# amigaDIP48_2025-07-20.net
KiCad netlist of a schematic drawn in Altium Designer
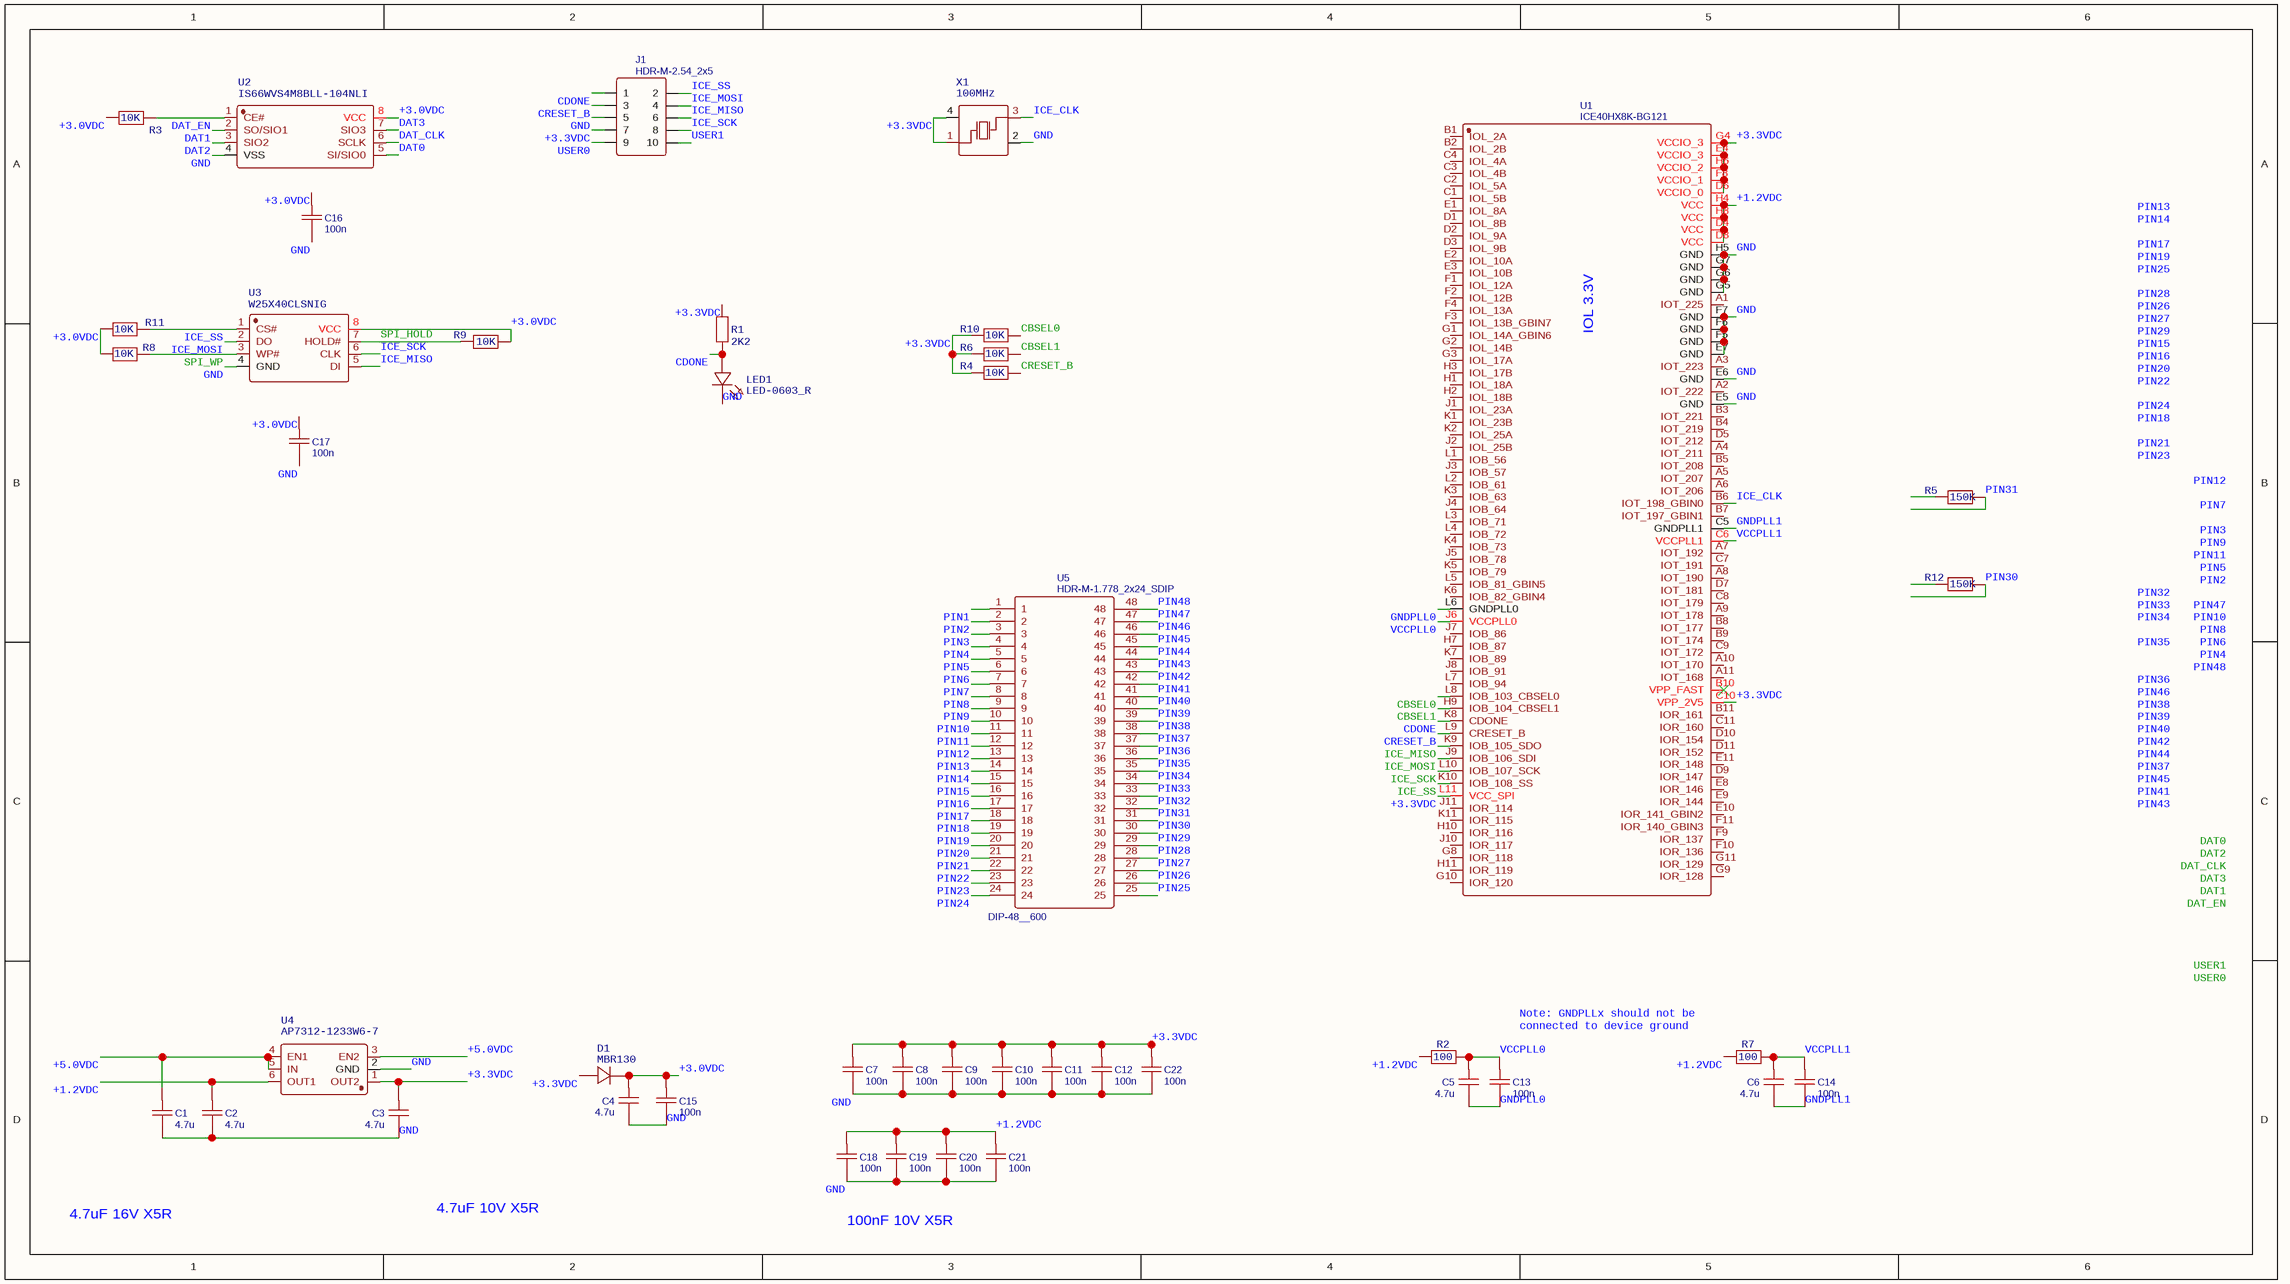
[diagram p0: amigaDIP48_2025-07-20.schdoc]

(export (version "E")
  (design (tool "Eeschema 10.0.6"))
  (components
    (comp (ref "C1")
      (value "4.7u")
      (fields
        (field (name "MANUFACTURER") "SAMSUNG(三星)")
        (field (name "MANUFACTURER PART") "CL05A475KP5NRNC")
        (field (name "CONTRIBUTOR") "LCSC")
      )
      (libsource (lib "") (part "root_0_4.7u__1"))
    )
    (comp (ref "C2")
      (value "4.7u")
      (fields
        (field (name "MANUFACTURER") "SAMSUNG(三星)")
        (field (name "MANUFACTURER PART") "CL05A475KP5NRNC")
        (field (name "CONTRIBUTOR") "LCSC")
      )
      (libsource (lib "") (part "root_0_4.7u__1"))
    )
    (comp (ref "C3")
      (value "4.7u")
      (fields
        (field (name "MANUFACTURER") "SAMSUNG(三星)")
        (field (name "MANUFACTURER PART") "CL05A475KP5NRNC")
        (field (name "CONTRIBUTOR") "LCSC")
      )
      (libsource (lib "altium-import") (part "root_0_4.7u_"))
    )
    (comp (ref "C4")
      (value "4.7u")
      (fields
        (field (name "MANUFACTURER") "SAMSUNG(三星)")
        (field (name "MANUFACTURER PART") "CL05A475KP5NRNC")
        (field (name "CONTRIBUTOR") "LCSC")
      )
      (libsource (lib "altium-import") (part "root_0_4.7u_"))
    )
    (comp (ref "C5")
      (value "4.7u")
      (fields
        (field (name "MANUFACTURER") "SAMSUNG(三星)")
        (field (name "MANUFACTURER PART") "CL05A475KP5NRNC")
        (field (name "CONTRIBUTOR") "LCSC")
      )
      (libsource (lib "altium-import") (part "root_0_4.7u_"))
    )
    (comp (ref "C6")
      (value "4.7u")
      (fields
        (field (name "MANUFACTURER") "SAMSUNG(三星)")
        (field (name "MANUFACTURER PART") "CL05A475KP5NRNC")
        (field (name "CONTRIBUTOR") "LCSC")
      )
      (libsource (lib "altium-import") (part "root_0_4.7u_"))
    )
    (comp (ref "C7")
      (value "100n")
      (fields
        (field (name "MANUFACTURER") "SAMSUNG(三星)")
        (field (name "MANUFACTURER PART") "CL03A104KP3NNNC")
      )
      (libsource (lib "altium-import") (part "root_1_100n_"))
    )
    (comp (ref "C8")
      (value "100n")
      (fields
        (field (name "MANUFACTURER") "SAMSUNG(三星)")
        (field (name "MANUFACTURER PART") "CL03A104KP3NNNC")
      )
      (libsource (lib "altium-import") (part "root_1_100n_"))
    )
    (comp (ref "C9")
      (value "100n")
      (fields
        (field (name "MANUFACTURER") "SAMSUNG(三星)")
        (field (name "MANUFACTURER PART") "CL03A104KP3NNNC")
      )
      (libsource (lib "altium-import") (part "root_1_100n_"))
    )
    (comp (ref "C10")
      (value "100n")
      (fields
        (field (name "MANUFACTURER") "SAMSUNG(三星)")
        (field (name "MANUFACTURER PART") "CL03A104KP3NNNC")
      )
      (libsource (lib "altium-import") (part "root_1_100n_"))
    )
    (comp (ref "C11")
      (value "100n")
      (fields
        (field (name "MANUFACTURER") "SAMSUNG(三星)")
        (field (name "MANUFACTURER PART") "CL03A104KP3NNNC")
      )
      (libsource (lib "altium-import") (part "root_1_100n_"))
    )
    (comp (ref "C12")
      (value "100n")
      (fields
        (field (name "MANUFACTURER") "SAMSUNG(三星)")
        (field (name "MANUFACTURER PART") "CL03A104KP3NNNC")
      )
      (libsource (lib "altium-import") (part "root_1_100n_"))
    )
    (comp (ref "C13")
      (value "100n")
      (fields
        (field (name "MANUFACTURER") "SAMSUNG(三星)")
        (field (name "MANUFACTURER PART") "CL03A104KP3NNNC")
      )
      (libsource (lib "altium-import") (part "root_1_100n_"))
    )
    (comp (ref "C14")
      (value "100n")
      (fields
        (field (name "MANUFACTURER") "SAMSUNG(三星)")
        (field (name "MANUFACTURER PART") "CL03A104KP3NNNC")
      )
      (libsource (lib "altium-import") (part "root_1_100n_"))
    )
    (comp (ref "C15")
      (value "100n")
      (fields
        (field (name "MANUFACTURER") "SAMSUNG(三星)")
        (field (name "MANUFACTURER PART") "CL03A104KP3NNNC")
      )
      (libsource (lib "altium-import") (part "root_1_100n_"))
    )
    (comp (ref "C16")
      (value "100n")
      (fields
        (field (name "MANUFACTURER") "SAMSUNG(三星)")
        (field (name "MANUFACTURER PART") "CL03A104KP3NNNC")
      )
      (libsource (lib "altium-import") (part "root_1_100n_"))
    )
    (comp (ref "C17")
      (value "100n")
      (fields
        (field (name "MANUFACTURER") "SAMSUNG(三星)")
        (field (name "MANUFACTURER PART") "CL03A104KP3NNNC")
      )
      (libsource (lib "altium-import") (part "root_1_100n_"))
    )
    (comp (ref "C18")
      (value "100n")
      (fields
        (field (name "MANUFACTURER") "SAMSUNG(三星)")
        (field (name "MANUFACTURER PART") "CL03A104KP3NNNC")
      )
      (libsource (lib "altium-import") (part "root_1_100n_"))
    )
    (comp (ref "C19")
      (value "100n")
      (fields
        (field (name "MANUFACTURER") "SAMSUNG(三星)")
        (field (name "MANUFACTURER PART") "CL03A104KP3NNNC")
      )
      (libsource (lib "altium-import") (part "root_1_100n_"))
    )
    (comp (ref "C20")
      (value "100n")
      (fields
        (field (name "MANUFACTURER") "SAMSUNG(三星)")
        (field (name "MANUFACTURER PART") "CL03A104KP3NNNC")
      )
      (libsource (lib "altium-import") (part "root_1_100n_"))
    )
    (comp (ref "C21")
      (value "100n")
      (fields
        (field (name "MANUFACTURER") "SAMSUNG(三星)")
        (field (name "MANUFACTURER PART") "CL03A104KP3NNNC")
      )
      (libsource (lib "altium-import") (part "root_1_100n_"))
    )
    (comp (ref "C22")
      (value "100n")
      (fields
        (field (name "MANUFACTURER") "SAMSUNG(三星)")
        (field (name "MANUFACTURER PART") "CL03A104KP3NNNC")
      )
      (libsource (lib "altium-import") (part "root_1_100n_"))
    )
    (comp (ref "D1")
      (value "MBR130")
      (fields (field (name "MANUFACTURER") "SK") (field (name "CONTRIBUTOR") "LCSC"))
      (libsource (lib "altium-import") (part "root_2_MBR130_"))
    )
    (comp (ref "J1")
      (value "HDR-M-2.54_2x5")
      (fields (field (name "CONTRIBUTOR") "LCEDA_Lib"))
      (libsource (lib "altium-import") (part "root_0_HDR-M-2.54_2x5_"))
    )
    (comp (ref "LED1")
      (value "LED-0603_R")
      (fields
        (field (name "MANUFACTURER") "EVERLIGHT(台湾亿光)")
        (field (name "MANUFACTURER PART") "19-217/R6C-AL1M2VY/3T")
        (field (name "CONTRIBUTOR") "LCEDA_01")
      )
      (libsource (lib "altium-import") (part "root_3_LED-0603_R_"))
    )
    (comp (ref "R1")
      (value "2K2")
      (fields
        (field (name "MANUFACTURER PART") "0402WGF1003TCE")
        (field (name "MANUFACTURER") "UniOhm")
        (field (name "CONTRIBUTOR") "LCEDA_Lib")
      )
      (libsource (lib "altium-import") (part "root_1_2K2_"))
    )
    (comp (ref "R2")
      (value "100")
      (fields
        (field (name "MANUFACTURER PART") "CR0201J100KQ15Z")
        (field (name "MANUFACTURER") "EVER OHMS(天二科技)")
        (field (name "CONTRIBUTOR") "LCEDA_Lib")
      )
      (libsource (lib "altium-import") (part "root_0_100_"))
    )
    (comp (ref "R3")
      (value "10K")
      (fields
        (field (name "MANUFACTURER PART") "CR0201F10K0Q15Z")
        (field (name "MANUFACTURER") "EVER OHMS(天二科技)")
        (field (name "CONTRIBUTOR") "LCEDA_Lib")
      )
      (libsource (lib "altium-import") (part "root_0_10K_"))
    )
    (comp (ref "R4")
      (value "10K")
      (fields
        (field (name "MANUFACTURER PART") "CR0201F10K0Q15Z")
        (field (name "MANUFACTURER") "EVER OHMS(天二科技)")
        (field (name "CONTRIBUTOR") "LCEDA_Lib")
      )
      (libsource (lib "altium-import") (part "root_0_10K_"))
    )
    (comp (ref "R5")
      (value "150K")
      (fields
        (field (name "MANUFACTURER PART") "WR02X154JAL")
        (field (name "MANUFACTURER") "Walsin(华新科)")
        (field (name "CONTRIBUTOR") "LCEDA_Lib")
      )
      (libsource (lib "altium-import") (part "root_0_150K_"))
    )
    (comp (ref "R6")
      (value "10K")
      (fields
        (field (name "MANUFACTURER PART") "CR0201F10K0Q15Z")
        (field (name "MANUFACTURER") "EVER OHMS(天二科技)")
        (field (name "CONTRIBUTOR") "LCEDA_Lib")
      )
      (libsource (lib "altium-import") (part "root_0_10K_"))
    )
    (comp (ref "R7")
      (value "100")
      (fields
        (field (name "MANUFACTURER PART") "CR0201J100KQ15Z")
        (field (name "MANUFACTURER") "EVER OHMS(天二科技)")
        (field (name "CONTRIBUTOR") "LCEDA_Lib")
      )
      (libsource (lib "altium-import") (part "root_0_100_"))
    )
    (comp (ref "R8")
      (value "10K")
      (fields
        (field (name "MANUFACTURER PART") "CR0201F10K0Q15Z")
        (field (name "MANUFACTURER") "EVER OHMS(天二科技)")
        (field (name "CONTRIBUTOR") "LCEDA_Lib")
      )
      (libsource (lib "altium-import") (part "root_0_10K_"))
    )
    (comp (ref "R9")
      (value "10K")
      (fields
        (field (name "MANUFACTURER PART") "CR0201F10K0Q15Z")
        (field (name "MANUFACTURER") "EVER OHMS(天二科技)")
        (field (name "CONTRIBUTOR") "LCEDA_Lib")
      )
      (libsource (lib "") (part "root_0_10K__1"))
    )
    (comp (ref "R10")
      (value "10K")
      (fields
        (field (name "MANUFACTURER PART") "CR0201F10K0Q15Z")
        (field (name "MANUFACTURER") "EVER OHMS(天二科技)")
        (field (name "CONTRIBUTOR") "LCEDA_Lib")
      )
      (libsource (lib "altium-import") (part "root_0_10K_"))
    )
    (comp (ref "R11")
      (value "10K")
      (fields
        (field (name "MANUFACTURER PART") "CR0201F10K0Q15Z")
        (field (name "MANUFACTURER") "EVER OHMS(天二科技)")
        (field (name "CONTRIBUTOR") "LCEDA_Lib")
      )
      (libsource (lib "altium-import") (part "root_0_10K_"))
    )
    (comp (ref "R12")
      (value "150K")
      (fields
        (field (name "MANUFACTURER PART") "WR02X154JAL")
        (field (name "MANUFACTURER") "Walsin(华新科)")
        (field (name "CONTRIBUTOR") "LCEDA_Lib")
      )
      (libsource (lib "altium-import") (part "root_0_150K_"))
    )
    (comp (ref "U1")
      (value "ICE40HX8K-BG121")
      (fields (field (name "MANUFACTURER") "LATTICE(莱迪思)") (field (name "CONTRIBUTOR") "LCSC"))
      (libsource (lib "altium-import") (part "root_0_ICE40HX8K-BG121_"))
    )
    (comp (ref "U2")
      (value "IS66WVS4M8BLL-104NLI")
      (fields (field (name "MANUFACTURER PART") "ESP-PSRAM64H") (field (name "CONTRIBUTOR") "LCSC"))
      (libsource (lib "altium-import") (part "root_0_IS66WVS4M8BLL-104NLI_"))
    )
    (comp (ref "U3")
      (value "W25X40CLSNIG")
      (fields (field (name "MANUFACTURER") "WINBOND"))
      (libsource (lib "altium-import") (part "root_0_W25X40CLSNIG_"))
    )
    (comp (ref "U4")
      (value "AP7312-1233W6-7")
      (fields
        (field (name "MANUFACTURER") "DIODES(美台)")
        (field (name "MANUFACTURER PART") "AP7312-1828W6-7")
        (field (name "CONTRIBUTOR") "lcsc")
      )
      (libsource (lib "altium-import") (part "root_2_AP7312-1233W6-7_"))
    )
    (comp (ref "U5")
      (value "HDR-M-1.778_2x24_SDIP")
      (fields (field (name "CONTRIBUTOR") "Renee"))
      (libsource (lib "altium-import") (part "root_0_HDR-M-1.778_2x24_SDIP_"))
    )
    (comp (ref "X1")
      (value "100MHz")
      (fields
        (field (name "MANUFACTURER") "TAITIEN Elec")
        (field (name "MANUFACTURER PART") "OXETDLJTNF-100.000000MHZ")
        (field (name "CONTRIBUTOR") "LCSC")
      )
      (libsource (lib "altium-import") (part "root_0_100MHz_"))
    )
  )
  (nets
    (net (code "1") (name "/+1.2VDC") (class "Default")
      (node (ref "C18") (pin "2") (pinfunction "2_2") (pintype "passive"))
      (node (ref "C19") (pin "2") (pinfunction "2_2") (pintype "passive"))
      (node (ref "C2") (pin "2") (pinfunction "2_2") (pintype "passive"))
      (node (ref "C20") (pin "2") (pinfunction "2_2") (pintype "passive"))
      (node (ref "C21") (pin "2") (pinfunction "2_2") (pintype "passive"))
      (node (ref "R2") (pin "1") (pinfunction "1_1") (pintype "passive"))
      (node (ref "R7") (pin "1") (pinfunction "1_1") (pintype "passive"))
      (node (ref "U1") (pin "D4") (pinfunction "VCC_D4") (pintype "passive"))
      (node (ref "U1") (pin "D8") (pinfunction "VCC_D8") (pintype "passive"))
      (node (ref "U1") (pin "H4") (pinfunction "VCC_H4") (pintype "passive"))
      (node (ref "U1") (pin "H8") (pinfunction "VCC_H8") (pintype "passive"))
      (node (ref "U4") (pin "6") (pinfunction "OUT1_6") (pintype "passive"))
    )
    (net (code "2") (name "/+3.0VDC") (class "Default")
      (node (ref "C15") (pin "2") (pinfunction "2_2") (pintype "passive"))
      (node (ref "C16") (pin "2") (pinfunction "2_2") (pintype "passive"))
      (node (ref "C17") (pin "2") (pinfunction "2_2") (pintype "passive"))
      (node (ref "C4") (pin "2") (pinfunction "2_2") (pintype "passive"))
      (node (ref "D1") (pin "1") (pinfunction "C_1") (pintype "passive"))
      (node (ref "R11") (pin "1") (pinfunction "1_1") (pintype "passive"))
      (node (ref "R3") (pin "1") (pinfunction "1_1") (pintype "passive"))
      (node (ref "R8") (pin "1") (pinfunction "1_1") (pintype "passive"))
      (node (ref "R9") (pin "1") (pinfunction "1_1") (pintype "passive"))
      (node (ref "U2") (pin "8") (pinfunction "VCC_8") (pintype "passive"))
      (node (ref "U3") (pin "8") (pinfunction "VCC_8") (pintype "passive"))
    )
    (net (code "3") (name "/+3.3VDC") (class "Default")
      (node (ref "C10") (pin "2") (pinfunction "2_2") (pintype "passive"))
      (node (ref "C11") (pin "2") (pinfunction "2_2") (pintype "passive"))
      (node (ref "C12") (pin "2") (pinfunction "2_2") (pintype "passive"))
      (node (ref "C22") (pin "2") (pinfunction "2_2") (pintype "passive"))
      (node (ref "C3") (pin "2") (pinfunction "2_2") (pintype "passive"))
      (node (ref "C7") (pin "2") (pinfunction "2_2") (pintype "passive"))
      (node (ref "C8") (pin "2") (pinfunction "2_2") (pintype "passive"))
      (node (ref "C9") (pin "2") (pinfunction "2_2") (pintype "passive"))
      (node (ref "D1") (pin "2") (pinfunction "A_2") (pintype "passive"))
      (node (ref "J1") (pin "7") (pinfunction "7_7") (pintype "passive"))
      (node (ref "R1") (pin "2") (pinfunction "2_2") (pintype "passive"))
      (node (ref "R10") (pin "1") (pinfunction "1_1") (pintype "passive"))
      (node (ref "R4") (pin "1") (pinfunction "1_1") (pintype "passive"))
      (node (ref "R6") (pin "1") (pinfunction "1_1") (pintype "passive"))
      (node (ref "U1") (pin "C10") (pinfunction "VPP_2V5_C10") (pintype "passive"))
      (node (ref "U1") (pin "D6") (pinfunction "VCCIO_0_D6") (pintype "passive"))
      (node (ref "U1") (pin "E4") (pinfunction "VCCIO_3_E4") (pintype "passive"))
      (node (ref "U1") (pin "F8") (pinfunction "VCCIO_1_F8") (pintype "passive"))
      (node (ref "U1") (pin "G4") (pinfunction "VCCIO_3_G4") (pintype "passive"))
      (node (ref "U1") (pin "H6") (pinfunction "VCCIO_2_H6") (pintype "passive"))
      (node (ref "U1") (pin "L11") (pinfunction "VCC_SPI_L11") (pintype "passive"))
      (node (ref "U4") (pin "1") (pinfunction "OUT2_1") (pintype "passive"))
      (node (ref "X1") (pin "1") (pinfunction "OSC1_1") (pintype "passive"))
      (node (ref "X1") (pin "4") (pinfunction "GND_4") (pintype "passive"))
    )
    (net (code "4") (name "/+5.0VDC") (class "Default")
      (node (ref "C1") (pin "2") (pinfunction "2_2") (pintype "passive"))
      (node (ref "U4") (pin "3") (pinfunction "EN2_3") (pintype "passive"))
      (node (ref "U4") (pin "4") (pinfunction "EN1_4") (pintype "passive"))
      (node (ref "U4") (pin "5") (pinfunction "IN_5") (pintype "passive"))
    )
    (net (code "5") (name "/CBSEL0") (class "Default")
      (node (ref "R10") (pin "2") (pinfunction "2_2") (pintype "passive"))
      (node (ref "U1") (pin "L8") (pinfunction "IOB_103_CBSEL0_L8") (pintype "passive"))
    )
    (net (code "6") (name "/CBSEL1") (class "Default")
      (node (ref "R6") (pin "2") (pinfunction "2_2") (pintype "passive"))
      (node (ref "U1") (pin "H9") (pinfunction "IOB_104_CBSEL1_H9") (pintype "passive"))
    )
    (net (code "7") (name "/CDONE") (class "Default")
      (node (ref "J1") (pin "1") (pinfunction "1_1") (pintype "passive"))
      (node (ref "LED1") (pin "1") (pinfunction "1_1") (pintype "passive"))
      (node (ref "R1") (pin "1") (pinfunction "1_1") (pintype "passive"))
      (node (ref "U1") (pin "K8") (pinfunction "CDONE_K8") (pintype "passive"))
    )
    (net (code "8") (name "/CRESET_B") (class "Default")
      (node (ref "J1") (pin "3") (pinfunction "3_3") (pintype "passive"))
      (node (ref "R4") (pin "2") (pinfunction "2_2") (pintype "passive"))
      (node (ref "U1") (pin "L9") (pinfunction "CRESET_B_L9") (pintype "passive"))
    )
    (net (code "9") (name "/DAT0") (class "Default")
      (node (ref "U2") (pin "5") (pinfunction "SI/SIO0_5") (pintype "passive"))
    )
    (net (code "10") (name "/DAT1") (class "Default")
      (node (ref "U2") (pin "2") (pinfunction "SO/SIO1_2") (pintype "passive"))
    )
    (net (code "11") (name "/DAT2") (class "Default")
      (node (ref "U2") (pin "3") (pinfunction "SIO2_3") (pintype "passive"))
    )
    (net (code "12") (name "/DAT3") (class "Default")
      (node (ref "U2") (pin "7") (pinfunction "SIO3_7") (pintype "passive"))
    )
    (net (code "13") (name "/DAT_CLK") (class "Default")
      (node (ref "U2") (pin "6") (pinfunction "SCLK_6") (pintype "passive"))
    )
    (net (code "14") (name "/DAT_EN") (class "Default")
      (node (ref "R3") (pin "2") (pinfunction "2_2") (pintype "passive"))
      (node (ref "U2") (pin "1") (pinfunction "CE#_1") (pintype "passive"))
    )
    (net (code "15") (name "/GND") (class "Default")
      (node (ref "C1") (pin "1") (pinfunction "1_1") (pintype "passive"))
      (node (ref "C10") (pin "1") (pinfunction "1_1") (pintype "passive"))
      (node (ref "C11") (pin "1") (pinfunction "1_1") (pintype "passive"))
      (node (ref "C12") (pin "1") (pinfunction "1_1") (pintype "passive"))
      (node (ref "C15") (pin "1") (pinfunction "1_1") (pintype "passive"))
      (node (ref "C16") (pin "1") (pinfunction "1_1") (pintype "passive"))
      (node (ref "C17") (pin "1") (pinfunction "1_1") (pintype "passive"))
      (node (ref "C18") (pin "1") (pinfunction "1_1") (pintype "passive"))
      (node (ref "C19") (pin "1") (pinfunction "1_1") (pintype "passive"))
      (node (ref "C2") (pin "1") (pinfunction "1_1") (pintype "passive"))
      (node (ref "C20") (pin "1") (pinfunction "1_1") (pintype "passive"))
      (node (ref "C21") (pin "1") (pinfunction "1_1") (pintype "passive"))
      (node (ref "C22") (pin "1") (pinfunction "1_1") (pintype "passive"))
      (node (ref "C3") (pin "1") (pinfunction "1_1") (pintype "passive"))
      (node (ref "C4") (pin "1") (pinfunction "1_1") (pintype "passive"))
      (node (ref "C7") (pin "1") (pinfunction "1_1") (pintype "passive"))
      (node (ref "C8") (pin "1") (pinfunction "1_1") (pintype "passive"))
      (node (ref "C9") (pin "1") (pinfunction "1_1") (pintype "passive"))
      (node (ref "J1") (pin "5") (pinfunction "5_5") (pintype "passive"))
      (node (ref "LED1") (pin "2") (pinfunction "2_2") (pintype "passive"))
      (node (ref "U1") (pin "E5") (pinfunction "GND_E5") (pintype "passive"))
      (node (ref "U1") (pin "E6") (pinfunction "GND_E6") (pintype "passive"))
      (node (ref "U1") (pin "E7") (pinfunction "GND_E7") (pintype "passive"))
      (node (ref "U1") (pin "F5") (pinfunction "GND_F5") (pintype "passive"))
      (node (ref "U1") (pin "F6") (pinfunction "GND_F6") (pintype "passive"))
      (node (ref "U1") (pin "F7") (pinfunction "GND_F7") (pintype "passive"))
      (node (ref "U1") (pin "G5") (pinfunction "GND_G5") (pintype "passive"))
      (node (ref "U1") (pin "G6") (pinfunction "GND_G6") (pintype "passive"))
      (node (ref "U1") (pin "G7") (pinfunction "GND_G7") (pintype "passive"))
      (node (ref "U1") (pin "H5") (pinfunction "GND_H5") (pintype "passive"))
      (node (ref "U2") (pin "4") (pinfunction "VSS_4") (pintype "passive"))
      (node (ref "U3") (pin "4") (pinfunction "GND_4") (pintype "passive"))
      (node (ref "U4") (pin "2") (pinfunction "GND_2") (pintype "passive"))
      (node (ref "X1") (pin "2") (pinfunction "GND_2") (pintype "passive"))
    )
    (net (code "16") (name "/GNDPLL0") (class "Default")
      (node (ref "C13") (pin "1") (pinfunction "1_1") (pintype "passive"))
      (node (ref "C5") (pin "1") (pinfunction "1_1") (pintype "passive"))
      (node (ref "U1") (pin "L6") (pinfunction "GNDPLL0_L6") (pintype "passive"))
    )
    (net (code "17") (name "/GNDPLL1") (class "Default")
      (node (ref "C14") (pin "1") (pinfunction "1_1") (pintype "passive"))
      (node (ref "C6") (pin "1") (pinfunction "1_1") (pintype "passive"))
      (node (ref "U1") (pin "C5") (pinfunction "GNDPLL1_C5") (pintype "passive"))
    )
    (net (code "18") (name "/ICE_CLK") (class "Default")
      (node (ref "U1") (pin "B6") (pinfunction "IOT_198_GBIN0_B6") (pintype "passive"))
      (node (ref "X1") (pin "3") (pinfunction "OSC2_3") (pintype "passive"))
    )
    (net (code "19") (name "/ICE_MISO") (class "Default")
      (node (ref "J1") (pin "6") (pinfunction "6_6") (pintype "passive"))
      (node (ref "U1") (pin "K9") (pinfunction "IOB_105_SDO_K9") (pintype "passive"))
      (node (ref "U3") (pin "5") (pinfunction "DI_5") (pintype "passive"))
    )
    (net (code "20") (name "/ICE_MOSI") (class "Default")
      (node (ref "J1") (pin "4") (pinfunction "4_4") (pintype "passive"))
      (node (ref "U1") (pin "J9") (pinfunction "IOB_106_SDI_J9") (pintype "passive"))
      (node (ref "U3") (pin "2") (pinfunction "DO_2") (pintype "passive"))
    )
    (net (code "21") (name "/ICE_SCK") (class "Default")
      (node (ref "J1") (pin "8") (pinfunction "8_8") (pintype "passive"))
      (node (ref "U1") (pin "L10") (pinfunction "IOB_107_SCK_L10") (pintype "passive"))
      (node (ref "U3") (pin "6") (pinfunction "CLK_6") (pintype "passive"))
    )
    (net (code "22") (name "/ICE_SS") (class "Default")
      (node (ref "J1") (pin "2") (pinfunction "2_2") (pintype "passive"))
      (node (ref "R11") (pin "2") (pinfunction "2_2") (pintype "passive"))
      (node (ref "U1") (pin "K10") (pinfunction "IOB_108_SS_K10") (pintype "passive"))
      (node (ref "U3") (pin "1") (pinfunction "CS#_1") (pintype "passive"))
    )
    (net (code "23") (name "/PIN1") (class "Default")
      (node (ref "U5") (pin "1") (pinfunction "1_1") (pintype "passive"))
    )
    (net (code "24") (name "/PIN2") (class "Default")
      (node (ref "U5") (pin "2") (pinfunction "2_2") (pintype "passive"))
    )
    (net (code "25") (name "/PIN3") (class "Default")
      (node (ref "U5") (pin "3") (pinfunction "3_3") (pintype "passive"))
    )
    (net (code "26") (name "/PIN4") (class "Default")
      (node (ref "U5") (pin "4") (pinfunction "4_4") (pintype "passive"))
    )
    (net (code "27") (name "/PIN5") (class "Default")
      (node (ref "U5") (pin "5") (pinfunction "5_5") (pintype "passive"))
    )
    (net (code "28") (name "/PIN6") (class "Default")
      (node (ref "U5") (pin "6") (pinfunction "6_6") (pintype "passive"))
    )
    (net (code "29") (name "/PIN7") (class "Default")
      (node (ref "U5") (pin "7") (pinfunction "7_7") (pintype "passive"))
    )
    (net (code "30") (name "/PIN8") (class "Default")
      (node (ref "U5") (pin "8") (pinfunction "8_8") (pintype "passive"))
    )
    (net (code "31") (name "/PIN9") (class "Default")
      (node (ref "U5") (pin "9") (pinfunction "9_9") (pintype "passive"))
    )
    (net (code "32") (name "/PIN10") (class "Default")
      (node (ref "U5") (pin "10") (pinfunction "10_10") (pintype "passive"))
    )
    (net (code "33") (name "/PIN11") (class "Default")
      (node (ref "U5") (pin "11") (pinfunction "11_11") (pintype "passive"))
    )
    (net (code "34") (name "/PIN12") (class "Default")
      (node (ref "U5") (pin "12") (pinfunction "12_12") (pintype "passive"))
    )
    (net (code "35") (name "/PIN13") (class "Default")
      (node (ref "U5") (pin "13") (pinfunction "13_13") (pintype "passive"))
    )
    (net (code "36") (name "/PIN14") (class "Default")
      (node (ref "U5") (pin "14") (pinfunction "14_14") (pintype "passive"))
    )
    (net (code "37") (name "/PIN15") (class "Default")
      (node (ref "U5") (pin "15") (pinfunction "15_15") (pintype "passive"))
    )
    (net (code "38") (name "/PIN16") (class "Default")
      (node (ref "U5") (pin "16") (pinfunction "16_16") (pintype "passive"))
    )
    (net (code "39") (name "/PIN17") (class "Default")
      (node (ref "U5") (pin "17") (pinfunction "17_17") (pintype "passive"))
    )
    (net (code "40") (name "/PIN18") (class "Default")
      (node (ref "U5") (pin "18") (pinfunction "18_18") (pintype "passive"))
    )
    (net (code "41") (name "/PIN19") (class "Default")
      (node (ref "U5") (pin "19") (pinfunction "19_19") (pintype "passive"))
    )
    (net (code "42") (name "/PIN20") (class "Default")
      (node (ref "U5") (pin "20") (pinfunction "20_20") (pintype "passive"))
    )
    (net (code "43") (name "/PIN21") (class "Default")
      (node (ref "U5") (pin "21") (pinfunction "21_21") (pintype "passive"))
    )
    (net (code "44") (name "/PIN22") (class "Default")
      (node (ref "U5") (pin "22") (pinfunction "22_22") (pintype "passive"))
    )
    (net (code "45") (name "/PIN23") (class "Default")
      (node (ref "U5") (pin "23") (pinfunction "23_23") (pintype "passive"))
    )
    (net (code "46") (name "/PIN24") (class "Default")
      (node (ref "U5") (pin "24") (pinfunction "24_24") (pintype "passive"))
    )
    (net (code "47") (name "/PIN25") (class "Default")
      (node (ref "U5") (pin "25") (pinfunction "25_25") (pintype "passive"))
    )
    (net (code "48") (name "/PIN26") (class "Default")
      (node (ref "U5") (pin "26") (pinfunction "26_26") (pintype "passive"))
    )
    (net (code "49") (name "/PIN27") (class "Default")
      (node (ref "U5") (pin "27") (pinfunction "27_27") (pintype "passive"))
    )
    (net (code "50") (name "/PIN28") (class "Default")
      (node (ref "U5") (pin "28") (pinfunction "28_28") (pintype "passive"))
    )
    (net (code "51") (name "/PIN29") (class "Default")
      (node (ref "U5") (pin "29") (pinfunction "29_29") (pintype "passive"))
    )
    (net (code "52") (name "/PIN30") (class "Default")
      (node (ref "R12") (pin "2") (pinfunction "2_2") (pintype "passive"))
      (node (ref "U5") (pin "30") (pinfunction "30_30") (pintype "passive"))
    )
    (net (code "53") (name "/PIN31") (class "Default")
      (node (ref "R5") (pin "2") (pinfunction "2_2") (pintype "passive"))
      (node (ref "U5") (pin "31") (pinfunction "31_31") (pintype "passive"))
    )
    (net (code "54") (name "/PIN32") (class "Default")
      (node (ref "U5") (pin "32") (pinfunction "32_32") (pintype "passive"))
    )
    (net (code "55") (name "/PIN33") (class "Default")
      (node (ref "U5") (pin "33") (pinfunction "33_33") (pintype "passive"))
    )
    (net (code "56") (name "/PIN34") (class "Default")
      (node (ref "U5") (pin "34") (pinfunction "34_34") (pintype "passive"))
    )
    (net (code "57") (name "/PIN35") (class "Default")
      (node (ref "U5") (pin "35") (pinfunction "35_35") (pintype "passive"))
    )
    (net (code "58") (name "/PIN36") (class "Default")
      (node (ref "U5") (pin "36") (pinfunction "36_36") (pintype "passive"))
    )
    (net (code "59") (name "/PIN37") (class "Default")
      (node (ref "U5") (pin "37") (pinfunction "37_37") (pintype "passive"))
    )
    (net (code "60") (name "/PIN38") (class "Default")
      (node (ref "U5") (pin "38") (pinfunction "38_38") (pintype "passive"))
    )
    (net (code "61") (name "/PIN39") (class "Default")
      (node (ref "U5") (pin "39") (pinfunction "39_39") (pintype "passive"))
    )
    (net (code "62") (name "/PIN40") (class "Default")
      (node (ref "U5") (pin "40") (pinfunction "40_40") (pintype "passive"))
    )
    (net (code "63") (name "/PIN41") (class "Default")
      (node (ref "U5") (pin "41") (pinfunction "41_41") (pintype "passive"))
    )
    (net (code "64") (name "/PIN42") (class "Default")
      (node (ref "U5") (pin "42") (pinfunction "42_42") (pintype "passive"))
    )
    (net (code "65") (name "/PIN43") (class "Default")
      (node (ref "U5") (pin "43") (pinfunction "43_43") (pintype "passive"))
    )
    (net (code "66") (name "/PIN44") (class "Default")
      (node (ref "U5") (pin "44") (pinfunction "44_44") (pintype "passive"))
    )
    (net (code "67") (name "/PIN45") (class "Default")
      (node (ref "U5") (pin "45") (pinfunction "45_45") (pintype "passive"))
    )
    (net (code "68") (name "/PIN46") (class "Default")
      (node (ref "U5") (pin "46") (pinfunction "46_46") (pintype "passive"))
    )
    (net (code "69") (name "/PIN47") (class "Default")
      (node (ref "U5") (pin "47") (pinfunction "47_47") (pintype "passive"))
    )
    (net (code "70") (name "/PIN48") (class "Default")
      (node (ref "U5") (pin "48") (pinfunction "48_48") (pintype "passive"))
    )
    (net (code "71") (name "/SPI_HOLD") (class "Default")
      (node (ref "R9") (pin "2") (pinfunction "2_2") (pintype "passive"))
      (node (ref "U3") (pin "7") (pinfunction "HOLD#_7") (pintype "passive"))
    )
    (net (code "72") (name "/SPI_WP") (class "Default")
      (node (ref "R8") (pin "2") (pinfunction "2_2") (pintype "passive"))
      (node (ref "U3") (pin "3") (pinfunction "WP#_3") (pintype "passive"))
    )
    (net (code "73") (name "/USER0") (class "Default")
      (node (ref "J1") (pin "9") (pinfunction "9_9") (pintype "passive"))
    )
    (net (code "74") (name "/USER1") (class "Default")
      (node (ref "J1") (pin "10") (pinfunction "10_10") (pintype "passive"))
    )
    (net (code "75") (name "/VCCPLL0") (class "Default")
      (node (ref "C13") (pin "2") (pinfunction "2_2") (pintype "passive"))
      (node (ref "C5") (pin "2") (pinfunction "2_2") (pintype "passive"))
      (node (ref "R2") (pin "2") (pinfunction "2_2") (pintype "passive"))
      (node (ref "U1") (pin "J6") (pinfunction "VCCPLL0_J6") (pintype "passive"))
    )
    (net (code "76") (name "/VCCPLL1") (class "Default")
      (node (ref "C14") (pin "2") (pinfunction "2_2") (pintype "passive"))
      (node (ref "C6") (pin "2") (pinfunction "2_2") (pintype "passive"))
      (node (ref "R7") (pin "2") (pinfunction "2_2") (pintype "passive"))
      (node (ref "U1") (pin "C6") (pinfunction "VCCPLL1_C6") (pintype "passive"))
    )
    (net (code "77") (name "unconnected-(R5-Pad1)") (class "Default")
      (node (ref "R5") (pin "1") (pinfunction "1_1") (pintype "passive"))
    )
    (net (code "78") (name "unconnected-(R12-Pad1)") (class "Default")
      (node (ref "R12") (pin "1") (pinfunction "1_1") (pintype "passive"))
    )
    (net (code "79") (name "unconnected-(U1-IOB_56-PadL1)") (class "Default")
      (node (ref "U1") (pin "L1") (pinfunction "IOB_56_L1") (pintype "passive"))
    )
    (net (code "80") (name "unconnected-(U1-IOB_57-PadJ3)") (class "Default")
      (node (ref "U1") (pin "J3") (pinfunction "IOB_57_J3") (pintype "passive"))
    )
    (net (code "81") (name "unconnected-(U1-IOB_61-PadL2)") (class "Default")
      (node (ref "U1") (pin "L2") (pinfunction "IOB_61_L2") (pintype "passive"))
    )
    (net (code "82") (name "unconnected-(U1-IOB_63-PadK3)") (class "Default")
      (node (ref "U1") (pin "K3") (pinfunction "IOB_63_K3") (pintype "passive"))
    )
    (net (code "83") (name "unconnected-(U1-IOB_64-PadJ4)") (class "Default")
      (node (ref "U1") (pin "J4") (pinfunction "IOB_64_J4") (pintype "passive"))
    )
    (net (code "84") (name "unconnected-(U1-IOB_71-PadL3)") (class "Default")
      (node (ref "U1") (pin "L3") (pinfunction "IOB_71_L3") (pintype "passive"))
    )
    (net (code "85") (name "unconnected-(U1-IOB_72-PadL4)") (class "Default")
      (node (ref "U1") (pin "L4") (pinfunction "IOB_72_L4") (pintype "passive"))
    )
    (net (code "86") (name "unconnected-(U1-IOB_73-PadK4)") (class "Default")
      (node (ref "U1") (pin "K4") (pinfunction "IOB_73_K4") (pintype "passive"))
    )
    (net (code "87") (name "unconnected-(U1-IOB_78-PadJ5)") (class "Default")
      (node (ref "U1") (pin "J5") (pinfunction "IOB_78_J5") (pintype "passive"))
    )
    (net (code "88") (name "unconnected-(U1-IOB_79-PadK5)") (class "Default")
      (node (ref "U1") (pin "K5") (pinfunction "IOB_79_K5") (pintype "passive"))
    )
    (net (code "89") (name "unconnected-(U1-IOB_81_GBIN5-PadL5)") (class "Default")
      (node (ref "U1") (pin "L5") (pinfunction "IOB_81_GBIN5_L5") (pintype "passive"))
    )
    (net (code "90") (name "unconnected-(U1-IOB_82_GBIN4-PadK6)") (class "Default")
      (node (ref "U1") (pin "K6") (pinfunction "IOB_82_GBIN4_K6") (pintype "passive"))
    )
    (net (code "91") (name "unconnected-(U1-IOB_86-PadJ7)") (class "Default")
      (node (ref "U1") (pin "J7") (pinfunction "IOB_86_J7") (pintype "passive"))
    )
    (net (code "92") (name "unconnected-(U1-IOB_87-PadH7)") (class "Default")
      (node (ref "U1") (pin "H7") (pinfunction "IOB_87_H7") (pintype "passive"))
    )
    (net (code "93") (name "unconnected-(U1-IOB_89-PadK7)") (class "Default")
      (node (ref "U1") (pin "K7") (pinfunction "IOB_89_K7") (pintype "passive"))
    )
    (net (code "94") (name "unconnected-(U1-IOB_91-PadJ8)") (class "Default")
      (node (ref "U1") (pin "J8") (pinfunction "IOB_91_J8") (pintype "passive"))
    )
    (net (code "95") (name "unconnected-(U1-IOB_94-PadL7)") (class "Default")
      (node (ref "U1") (pin "L7") (pinfunction "IOB_94_L7") (pintype "passive"))
    )
    (net (code "96") (name "unconnected-(U1-IOL_2A-PadB1)") (class "Default")
      (node (ref "U1") (pin "B1") (pinfunction "IOL_2A_B1") (pintype "passive"))
    )
    (net (code "97") (name "unconnected-(U1-IOL_2B-PadB2)") (class "Default")
      (node (ref "U1") (pin "B2") (pinfunction "IOL_2B_B2") (pintype "passive"))
    )
    (net (code "98") (name "unconnected-(U1-IOL_4A-PadC4)") (class "Default")
      (node (ref "U1") (pin "C4") (pinfunction "IOL_4A_C4") (pintype "passive"))
    )
    (net (code "99") (name "unconnected-(U1-IOL_4B-PadC3)") (class "Default")
      (node (ref "U1") (pin "C3") (pinfunction "IOL_4B_C3") (pintype "passive"))
    )
    (net (code "100") (name "unconnected-(U1-IOL_5A-PadC2)") (class "Default")
      (node (ref "U1") (pin "C2") (pinfunction "IOL_5A_C2") (pintype "passive"))
    )
    (net (code "101") (name "unconnected-(U1-IOL_5B-PadC1)") (class "Default")
      (node (ref "U1") (pin "C1") (pinfunction "IOL_5B_C1") (pintype "passive"))
    )
    (net (code "102") (name "unconnected-(U1-IOL_8A-PadE1)") (class "Default")
      (node (ref "U1") (pin "E1") (pinfunction "IOL_8A_E1") (pintype "passive"))
    )
    (net (code "103") (name "unconnected-(U1-IOL_8B-PadD1)") (class "Default")
      (node (ref "U1") (pin "D1") (pinfunction "IOL_8B_D1") (pintype "passive"))
    )
    (net (code "104") (name "unconnected-(U1-IOL_9A-PadD2)") (class "Default")
      (node (ref "U1") (pin "D2") (pinfunction "IOL_9A_D2") (pintype "passive"))
    )
    (net (code "105") (name "unconnected-(U1-IOL_9B-PadD3)") (class "Default")
      (node (ref "U1") (pin "D3") (pinfunction "IOL_9B_D3") (pintype "passive"))
    )
    (net (code "106") (name "unconnected-(U1-IOL_10A-PadE2)") (class "Default")
      (node (ref "U1") (pin "E2") (pinfunction "IOL_10A_E2") (pintype "passive"))
    )
    (net (code "107") (name "unconnected-(U1-IOL_10B-PadE3)") (class "Default")
      (node (ref "U1") (pin "E3") (pinfunction "IOL_10B_E3") (pintype "passive"))
    )
    (net (code "108") (name "unconnected-(U1-IOL_12A-PadF1)") (class "Default")
      (node (ref "U1") (pin "F1") (pinfunction "IOL_12A_F1") (pintype "passive"))
    )
    (net (code "109") (name "unconnected-(U1-IOL_12B-PadF2)") (class "Default")
      (node (ref "U1") (pin "F2") (pinfunction "IOL_12B_F2") (pintype "passive"))
    )
    (net (code "110") (name "unconnected-(U1-IOL_13A-PadF4)") (class "Default")
      (node (ref "U1") (pin "F4") (pinfunction "IOL_13A_F4") (pintype "passive"))
    )
    (net (code "111") (name "unconnected-(U1-IOL_13B_GBIN7-PadF3)") (class "Default")
      (node (ref "U1") (pin "F3") (pinfunction "IOL_13B_GBIN7_F3") (pintype "passive"))
    )
    (net (code "112") (name "unconnected-(U1-IOL_14A_GBIN6-PadG1)") (class "Default")
      (node (ref "U1") (pin "G1") (pinfunction "IOL_14A_GBIN6_G1") (pintype "passive"))
    )
    (net (code "113") (name "unconnected-(U1-IOL_14B-PadG2)") (class "Default")
      (node (ref "U1") (pin "G2") (pinfunction "IOL_14B_G2") (pintype "passive"))
    )
    (net (code "114") (name "unconnected-(U1-IOL_17A-PadG3)") (class "Default")
      (node (ref "U1") (pin "G3") (pinfunction "IOL_17A_G3") (pintype "passive"))
    )
    (net (code "115") (name "unconnected-(U1-IOL_17B-PadH3)") (class "Default")
      (node (ref "U1") (pin "H3") (pinfunction "IOL_17B_H3") (pintype "passive"))
    )
    (net (code "116") (name "unconnected-(U1-IOL_18A-PadH1)") (class "Default")
      (node (ref "U1") (pin "H1") (pinfunction "IOL_18A_H1") (pintype "passive"))
    )
    (net (code "117") (name "unconnected-(U1-IOL_18B-PadH2)") (class "Default")
      (node (ref "U1") (pin "H2") (pinfunction "IOL_18B_H2") (pintype "passive"))
    )
    (net (code "118") (name "unconnected-(U1-IOL_23A-PadJ1)") (class "Default")
      (node (ref "U1") (pin "J1") (pinfunction "IOL_23A_J1") (pintype "passive"))
    )
    (net (code "119") (name "unconnected-(U1-IOL_23B-PadK1)") (class "Default")
      (node (ref "U1") (pin "K1") (pinfunction "IOL_23B_K1") (pintype "passive"))
    )
    (net (code "120") (name "unconnected-(U1-IOL_25A-PadK2)") (class "Default")
      (node (ref "U1") (pin "K2") (pinfunction "IOL_25A_K2") (pintype "passive"))
    )
    (net (code "121") (name "unconnected-(U1-IOL_25B-PadJ2)") (class "Default")
      (node (ref "U1") (pin "J2") (pinfunction "IOL_25B_J2") (pintype "passive"))
    )
    (net (code "122") (name "unconnected-(U1-IOR_114-PadJ11)") (class "Default")
      (node (ref "U1") (pin "J11") (pinfunction "IOR_114_J11") (pintype "passive"))
    )
    (net (code "123") (name "unconnected-(U1-IOR_115-PadK11)") (class "Default")
      (node (ref "U1") (pin "K11") (pinfunction "IOR_115_K11") (pintype "passive"))
    )
    (net (code "124") (name "unconnected-(U1-IOR_116-PadH10)") (class "Default")
      (node (ref "U1") (pin "H10") (pinfunction "IOR_116_H10") (pintype "passive"))
    )
    (net (code "125") (name "unconnected-(U1-IOR_117-PadJ10)") (class "Default")
      (node (ref "U1") (pin "J10") (pinfunction "IOR_117_J10") (pintype "passive"))
    )
    (net (code "126") (name "unconnected-(U1-IOR_118-PadG8)") (class "Default")
      (node (ref "U1") (pin "G8") (pinfunction "IOR_118_G8") (pintype "passive"))
    )
    (net (code "127") (name "unconnected-(U1-IOR_119-PadH11)") (class "Default")
      (node (ref "U1") (pin "H11") (pinfunction "IOR_119_H11") (pintype "passive"))
    )
    (net (code "128") (name "unconnected-(U1-IOR_120-PadG10)") (class "Default")
      (node (ref "U1") (pin "G10") (pinfunction "IOR_120_G10") (pintype "passive"))
    )
    (net (code "129") (name "unconnected-(U1-IOR_128-PadG9)") (class "Default")
      (node (ref "U1") (pin "G9") (pinfunction "IOR_128_G9") (pintype "passive"))
    )
    (net (code "130") (name "unconnected-(U1-IOR_129-PadG11)") (class "Default")
      (node (ref "U1") (pin "G11") (pinfunction "IOR_129_G11") (pintype "passive"))
    )
    (net (code "131") (name "unconnected-(U1-IOR_136-PadF10)") (class "Default")
      (node (ref "U1") (pin "F10") (pinfunction "IOR_136_F10") (pintype "passive"))
    )
    (net (code "132") (name "unconnected-(U1-IOR_137-PadF9)") (class "Default")
      (node (ref "U1") (pin "F9") (pinfunction "IOR_137_F9") (pintype "passive"))
    )
    (net (code "133") (name "unconnected-(U1-IOR_140_GBIN3-PadF11)") (class "Default")
      (node (ref "U1") (pin "F11") (pinfunction "IOR_140_GBIN3_F11") (pintype "passive"))
    )
    (net (code "134") (name "unconnected-(U1-IOR_141_GBIN2-PadE10)") (class "Default")
      (node (ref "U1") (pin "E10") (pinfunction "IOR_141_GBIN2_E10") (pintype "passive"))
    )
    (net (code "135") (name "unconnected-(U1-IOR_144-PadE9)") (class "Default")
      (node (ref "U1") (pin "E9") (pinfunction "IOR_144_E9") (pintype "passive"))
    )
    (net (code "136") (name "unconnected-(U1-IOR_146-PadE8)") (class "Default")
      (node (ref "U1") (pin "E8") (pinfunction "IOR_146_E8") (pintype "passive"))
    )
    (net (code "137") (name "unconnected-(U1-IOR_147-PadD9)") (class "Default")
      (node (ref "U1") (pin "D9") (pinfunction "IOR_147_D9") (pintype "passive"))
    )
    (net (code "138") (name "unconnected-(U1-IOR_148-PadE11)") (class "Default")
      (node (ref "U1") (pin "E11") (pinfunction "IOR_148_E11") (pintype "passive"))
    )
    (net (code "139") (name "unconnected-(U1-IOR_152-PadD11)") (class "Default")
      (node (ref "U1") (pin "D11") (pinfunction "IOR_152_D11") (pintype "passive"))
    )
    (net (code "140") (name "unconnected-(U1-IOR_154-PadD10)") (class "Default")
      (node (ref "U1") (pin "D10") (pinfunction "IOR_154_D10") (pintype "passive"))
    )
    (net (code "141") (name "unconnected-(U1-IOR_160-PadC11)") (class "Default")
      (node (ref "U1") (pin "C11") (pinfunction "IOR_160_C11") (pintype "passive"))
    )
    (net (code "142") (name "unconnected-(U1-IOR_161-PadB11)") (class "Default")
      (node (ref "U1") (pin "B11") (pinfunction "IOR_161_B11") (pintype "passive"))
    )
    (net (code "143") (name "unconnected-(U1-IOT_168-PadA11)") (class "Default")
      (node (ref "U1") (pin "A11") (pinfunction "IOT_168_A11") (pintype "passive"))
    )
    (net (code "144") (name "unconnected-(U1-IOT_170-PadA10)") (class "Default")
      (node (ref "U1") (pin "A10") (pinfunction "IOT_170_A10") (pintype "passive"))
    )
    (net (code "145") (name "unconnected-(U1-IOT_172-PadC9)") (class "Default")
      (node (ref "U1") (pin "C9") (pinfunction "IOT_172_C9") (pintype "passive"))
    )
    (net (code "146") (name "unconnected-(U1-IOT_174-PadB9)") (class "Default")
      (node (ref "U1") (pin "B9") (pinfunction "IOT_174_B9") (pintype "passive"))
    )
    (net (code "147") (name "unconnected-(U1-IOT_177-PadB8)") (class "Default")
      (node (ref "U1") (pin "B8") (pinfunction "IOT_177_B8") (pintype "passive"))
    )
    (net (code "148") (name "unconnected-(U1-IOT_178-PadA9)") (class "Default")
      (node (ref "U1") (pin "A9") (pinfunction "IOT_178_A9") (pintype "passive"))
    )
    (net (code "149") (name "unconnected-(U1-IOT_179-PadC8)") (class "Default")
      (node (ref "U1") (pin "C8") (pinfunction "IOT_179_C8") (pintype "passive"))
    )
    (net (code "150") (name "unconnected-(U1-IOT_181-PadD7)") (class "Default")
      (node (ref "U1") (pin "D7") (pinfunction "IOT_181_D7") (pintype "passive"))
    )
    (net (code "151") (name "unconnected-(U1-IOT_190-PadA8)") (class "Default")
      (node (ref "U1") (pin "A8") (pinfunction "IOT_190_A8") (pintype "passive"))
    )
    (net (code "152") (name "unconnected-(U1-IOT_191-PadC7)") (class "Default")
      (node (ref "U1") (pin "C7") (pinfunction "IOT_191_C7") (pintype "passive"))
    )
    (net (code "153") (name "unconnected-(U1-IOT_192-PadA7)") (class "Default")
      (node (ref "U1") (pin "A7") (pinfunction "IOT_192_A7") (pintype "passive"))
    )
    (net (code "154") (name "unconnected-(U1-IOT_197_GBIN1-PadB7)") (class "Default")
      (node (ref "U1") (pin "B7") (pinfunction "IOT_197_GBIN1_B7") (pintype "passive"))
    )
    (net (code "155") (name "unconnected-(U1-IOT_206-PadA6)") (class "Default")
      (node (ref "U1") (pin "A6") (pinfunction "IOT_206_A6") (pintype "passive"))
    )
    (net (code "156") (name "unconnected-(U1-IOT_207-PadA5)") (class "Default")
      (node (ref "U1") (pin "A5") (pinfunction "IOT_207_A5") (pintype "passive"))
    )
    (net (code "157") (name "unconnected-(U1-IOT_208-PadB5)") (class "Default")
      (node (ref "U1") (pin "B5") (pinfunction "IOT_208_B5") (pintype "passive"))
    )
    (net (code "158") (name "unconnected-(U1-IOT_211-PadA4)") (class "Default")
      (node (ref "U1") (pin "A4") (pinfunction "IOT_211_A4") (pintype "passive"))
    )
    (net (code "159") (name "unconnected-(U1-IOT_212-PadD5)") (class "Default")
      (node (ref "U1") (pin "D5") (pinfunction "IOT_212_D5") (pintype "passive"))
    )
    (net (code "160") (name "unconnected-(U1-IOT_219-PadB4)") (class "Default")
      (node (ref "U1") (pin "B4") (pinfunction "IOT_219_B4") (pintype "passive"))
    )
    (net (code "161") (name "unconnected-(U1-IOT_221-PadB3)") (class "Default")
      (node (ref "U1") (pin "B3") (pinfunction "IOT_221_B3") (pintype "passive"))
    )
    (net (code "162") (name "unconnected-(U1-IOT_222-PadA2)") (class "Default")
      (node (ref "U1") (pin "A2") (pinfunction "IOT_222_A2") (pintype "passive"))
    )
    (net (code "163") (name "unconnected-(U1-IOT_223-PadA3)") (class "Default")
      (node (ref "U1") (pin "A3") (pinfunction "IOT_223_A3") (pintype "passive"))
    )
    (net (code "164") (name "unconnected-(U1-IOT_225-PadA1)") (class "Default")
      (node (ref "U1") (pin "A1") (pinfunction "IOT_225_A1") (pintype "passive"))
    )
    (net (code "165") (name "unconnected-(U1-VPP_FAST-PadB10)") (class "Default")
      (node (ref "U1") (pin "B10") (pinfunction "VPP_FAST_B10") (pintype "passive+no_connect"))
    )
  )
)
